# common.net
KiCad netlist of a schematic drawn in EAGLE
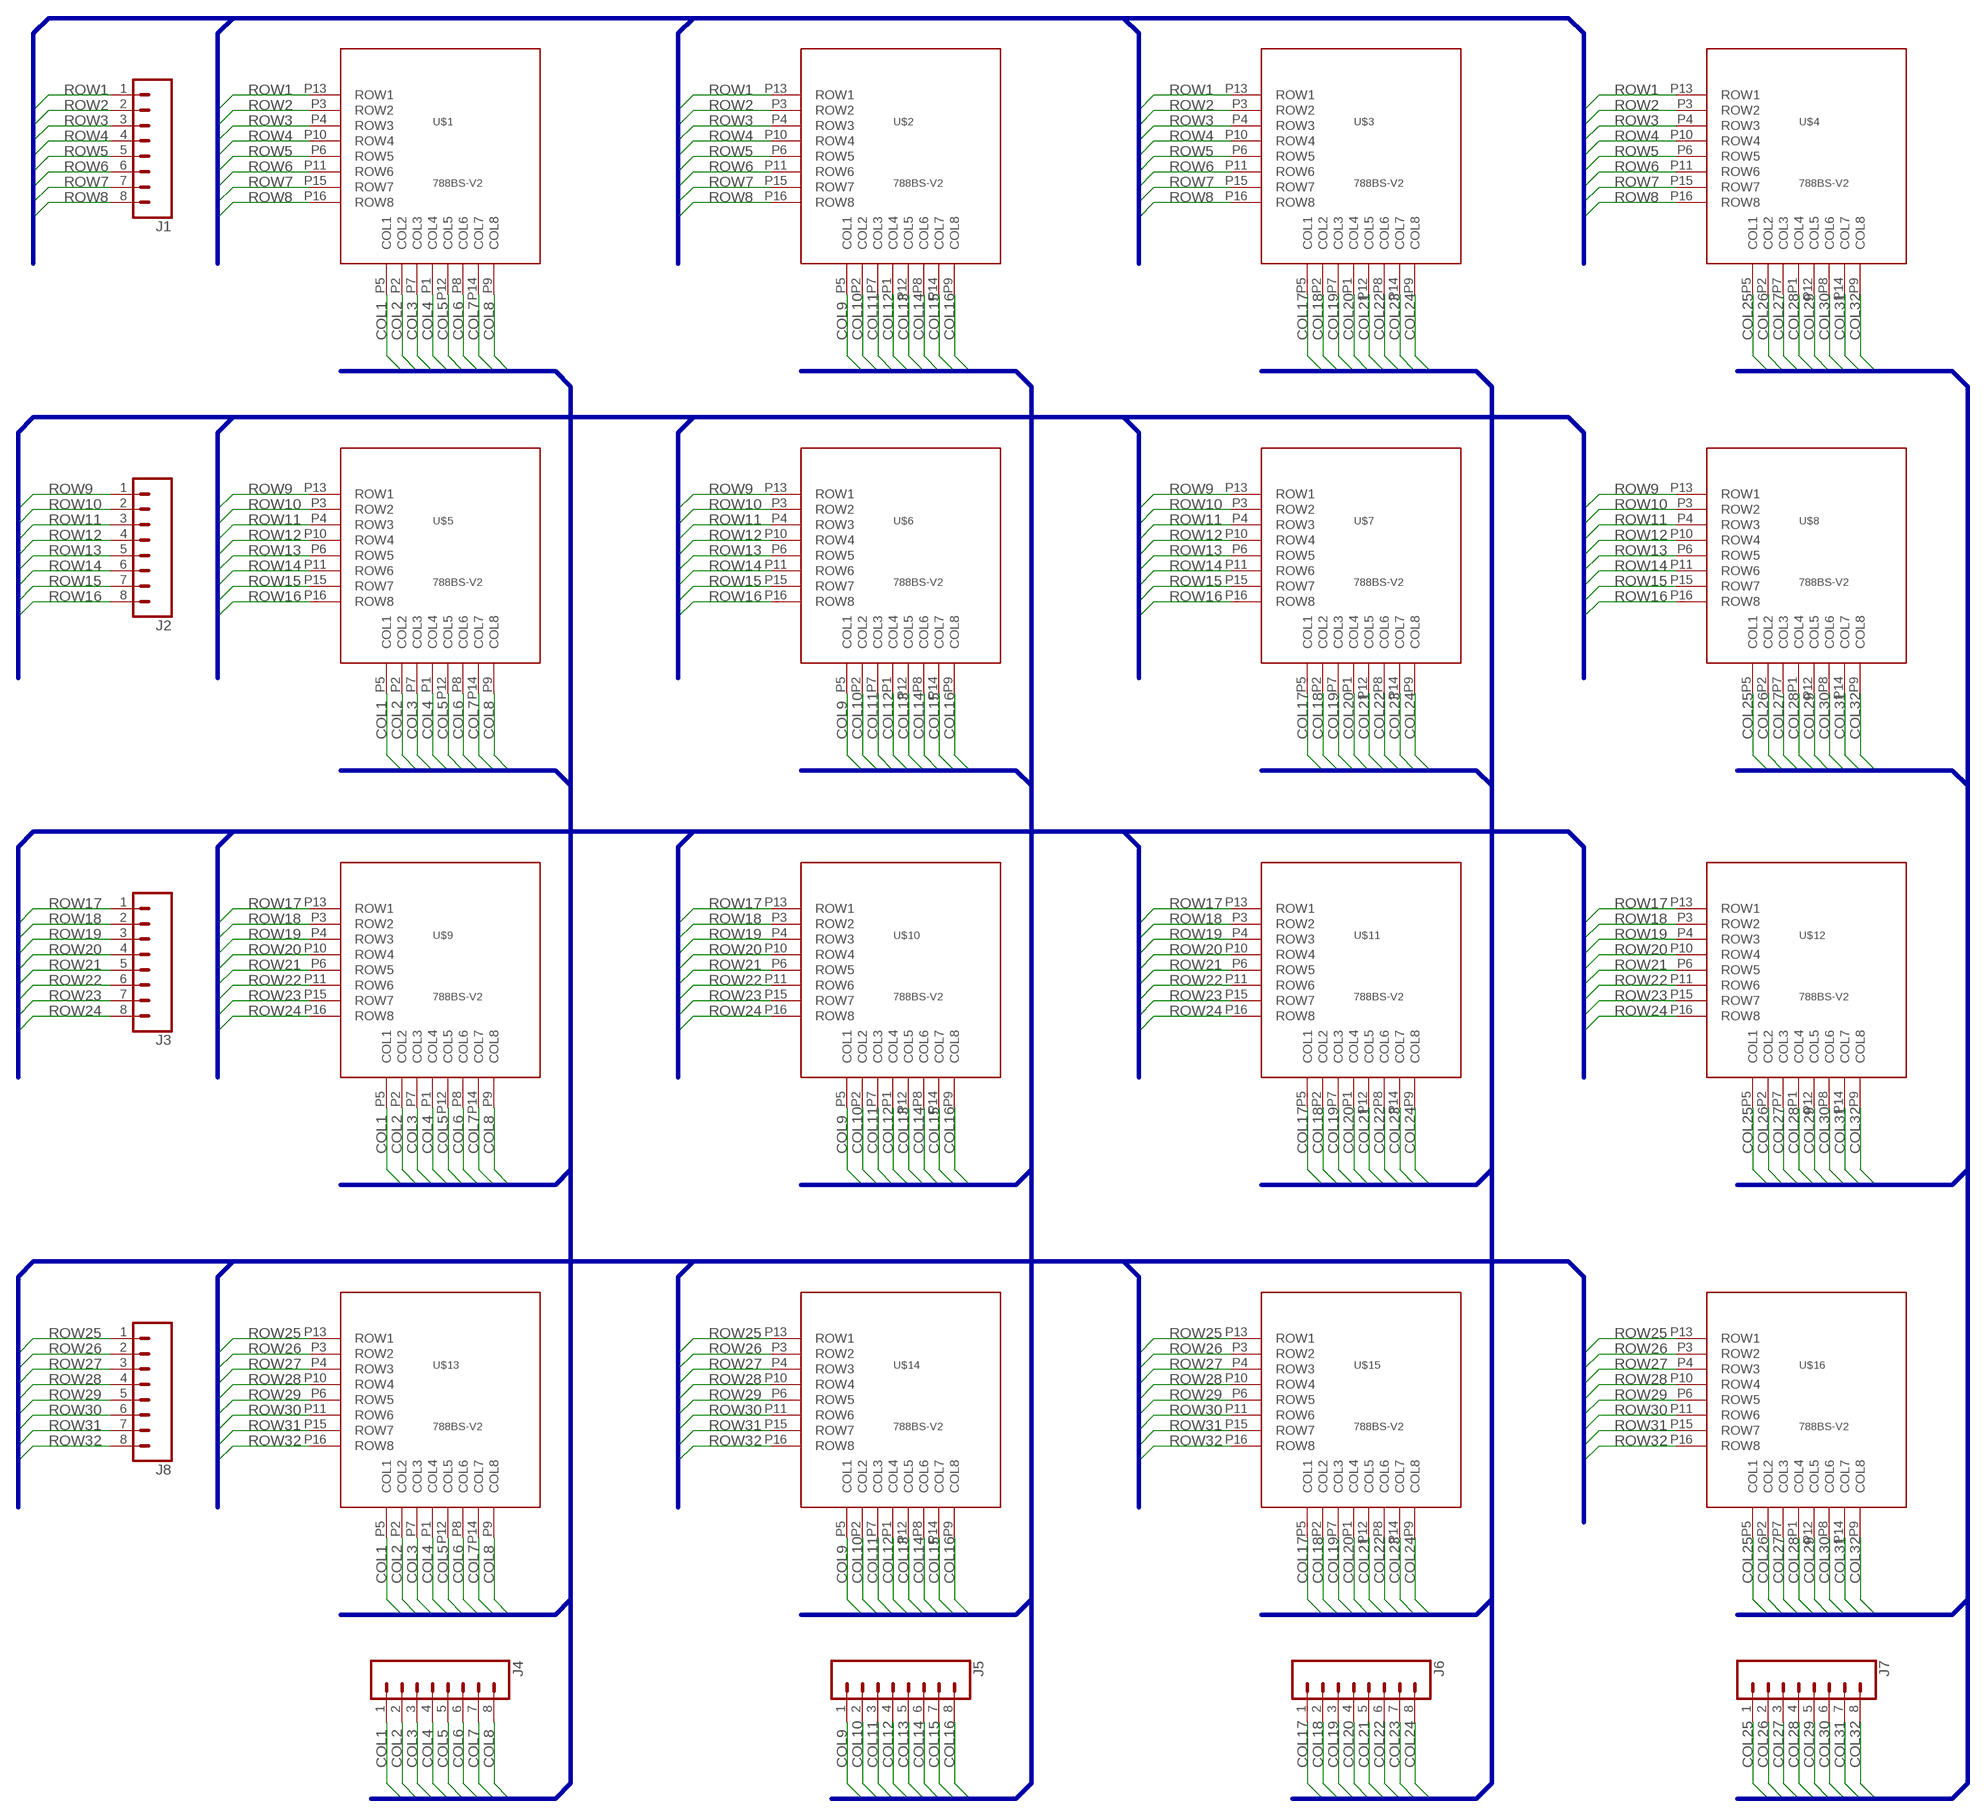
[diagram p0: schematic, sheet 1]

(export (version "E")
  (design (tool "Eeschema 10.0.6"))
  (components
    (comp (ref "J1")
      (value "CONN_08\"")
      (footprint "eagle-import:1X08")
      (libsource (lib "eagle-import") (part "CONN_08{dblquote}"))
    )
    (comp (ref "J2")
      (value "CONN_08\"")
      (footprint "eagle-import:1X08")
      (libsource (lib "eagle-import") (part "CONN_08{dblquote}"))
    )
    (comp (ref "J3")
      (value "CONN_08\"")
      (footprint "eagle-import:1X08")
      (libsource (lib "eagle-import") (part "CONN_08{dblquote}"))
    )
    (comp (ref "J4")
      (value "CONN_08\"")
      (footprint "eagle-import:1X08")
      (libsource (lib "eagle-import") (part "CONN_08{dblquote}"))
    )
    (comp (ref "J5")
      (value "CONN_08\"")
      (footprint "eagle-import:1X08")
      (libsource (lib "eagle-import") (part "CONN_08{dblquote}"))
    )
    (comp (ref "J6")
      (value "CONN_08\"")
      (footprint "eagle-import:1X08")
      (libsource (lib "eagle-import") (part "CONN_08{dblquote}"))
    )
    (comp (ref "J7")
      (value "CONN_08\"")
      (footprint "eagle-import:1X08")
      (libsource (lib "eagle-import") (part "CONN_08{dblquote}"))
    )
    (comp (ref "J8")
      (value "CONN_08\"")
      (footprint "eagle-import:1X08")
      (libsource (lib "eagle-import") (part "CONN_08{dblquote}"))
    )
    (comp (ref "U$1")
      (value "788BS-V2")
      (footprint "eagle-import:788BS8X81.9MM-V2")
      (libsource (lib "eagle-import") (part "788BS-V2"))
    )
    (comp (ref "U$2")
      (value "788BS-V2")
      (footprint "eagle-import:788BS8X81.9MM-V2")
      (libsource (lib "eagle-import") (part "788BS-V2"))
    )
    (comp (ref "U$3")
      (value "788BS-V2")
      (footprint "eagle-import:788BS8X81.9MM-V2")
      (libsource (lib "eagle-import") (part "788BS-V2"))
    )
    (comp (ref "U$4")
      (value "788BS-V2")
      (footprint "eagle-import:788BS8X81.9MM-V2")
      (libsource (lib "eagle-import") (part "788BS-V2"))
    )
    (comp (ref "U$5")
      (value "788BS-V2")
      (footprint "eagle-import:788BS8X81.9MM-V2")
      (libsource (lib "eagle-import") (part "788BS-V2"))
    )
    (comp (ref "U$6")
      (value "788BS-V2")
      (footprint "eagle-import:788BS8X81.9MM-V2")
      (libsource (lib "eagle-import") (part "788BS-V2"))
    )
    (comp (ref "U$7")
      (value "788BS-V2")
      (footprint "eagle-import:788BS8X81.9MM-V2")
      (libsource (lib "eagle-import") (part "788BS-V2"))
    )
    (comp (ref "U$8")
      (value "788BS-V2")
      (footprint "eagle-import:788BS8X81.9MM-V2")
      (libsource (lib "eagle-import") (part "788BS-V2"))
    )
    (comp (ref "U$9")
      (value "788BS-V2")
      (footprint "eagle-import:788BS8X81.9MM-V2")
      (libsource (lib "eagle-import") (part "788BS-V2"))
    )
    (comp (ref "U$10")
      (value "788BS-V2")
      (footprint "eagle-import:788BS8X81.9MM-V2")
      (libsource (lib "eagle-import") (part "788BS-V2"))
    )
    (comp (ref "U$11")
      (value "788BS-V2")
      (footprint "eagle-import:788BS8X81.9MM-V2")
      (libsource (lib "eagle-import") (part "788BS-V2"))
    )
    (comp (ref "U$12")
      (value "788BS-V2")
      (footprint "eagle-import:788BS8X81.9MM-V2")
      (libsource (lib "eagle-import") (part "788BS-V2"))
    )
    (comp (ref "U$13")
      (value "788BS-V2")
      (footprint "eagle-import:788BS8X81.9MM-V2")
      (libsource (lib "eagle-import") (part "788BS-V2"))
    )
    (comp (ref "U$14")
      (value "788BS-V2")
      (footprint "eagle-import:788BS8X81.9MM-V2")
      (libsource (lib "eagle-import") (part "788BS-V2"))
    )
    (comp (ref "U$15")
      (value "788BS-V2")
      (footprint "eagle-import:788BS8X81.9MM-V2")
      (libsource (lib "eagle-import") (part "788BS-V2"))
    )
    (comp (ref "U$16")
      (value "788BS-V2")
      (footprint "eagle-import:788BS8X81.9MM-V2")
      (libsource (lib "eagle-import") (part "788BS-V2"))
    )
  )
  (nets
    (net (code "57") (name "/COL1") (class "Default")
      (node (ref "J4") (pin "1") (pinfunction "1_1") (pintype "passive"))
      (node (ref "U$1") (pin "P5") (pinfunction "COL1_P5") (pintype "bidirectional"))
      (node (ref "U$13") (pin "P5") (pinfunction "COL1_P5") (pintype "bidirectional"))
      (node (ref "U$5") (pin "P5") (pinfunction "COL1_P5") (pintype "bidirectional"))
      (node (ref "U$9") (pin "P5") (pinfunction "COL1_P5") (pintype "bidirectional"))
    )
    (net (code "58") (name "/COL2") (class "Default")
      (node (ref "J4") (pin "2") (pinfunction "2_2") (pintype "passive"))
      (node (ref "U$1") (pin "P2") (pinfunction "COL2_P2") (pintype "bidirectional"))
      (node (ref "U$13") (pin "P2") (pinfunction "COL2_P2") (pintype "bidirectional"))
      (node (ref "U$5") (pin "P2") (pinfunction "COL2_P2") (pintype "bidirectional"))
      (node (ref "U$9") (pin "P2") (pinfunction "COL2_P2") (pintype "bidirectional"))
    )
    (net (code "59") (name "/COL3") (class "Default")
      (node (ref "J4") (pin "3") (pinfunction "3_3") (pintype "passive"))
      (node (ref "U$1") (pin "P7") (pinfunction "COL3_P7") (pintype "bidirectional"))
      (node (ref "U$13") (pin "P7") (pinfunction "COL3_P7") (pintype "bidirectional"))
      (node (ref "U$5") (pin "P7") (pinfunction "COL3_P7") (pintype "bidirectional"))
      (node (ref "U$9") (pin "P7") (pinfunction "COL3_P7") (pintype "bidirectional"))
    )
    (net (code "60") (name "/COL4") (class "Default")
      (node (ref "J4") (pin "4") (pinfunction "4_4") (pintype "passive"))
      (node (ref "U$1") (pin "P1") (pinfunction "COL4_P1") (pintype "bidirectional"))
      (node (ref "U$13") (pin "P1") (pinfunction "COL4_P1") (pintype "bidirectional"))
      (node (ref "U$5") (pin "P1") (pinfunction "COL4_P1") (pintype "bidirectional"))
      (node (ref "U$9") (pin "P1") (pinfunction "COL4_P1") (pintype "bidirectional"))
    )
    (net (code "61") (name "/COL5") (class "Default")
      (node (ref "J4") (pin "5") (pinfunction "5_5") (pintype "passive"))
      (node (ref "U$1") (pin "P12") (pinfunction "COL5_P12") (pintype "bidirectional"))
      (node (ref "U$13") (pin "P12") (pinfunction "COL5_P12") (pintype "bidirectional"))
      (node (ref "U$5") (pin "P12") (pinfunction "COL5_P12") (pintype "bidirectional"))
      (node (ref "U$9") (pin "P12") (pinfunction "COL5_P12") (pintype "bidirectional"))
    )
    (net (code "62") (name "/COL6") (class "Default")
      (node (ref "J4") (pin "6") (pinfunction "6_6") (pintype "passive"))
      (node (ref "U$1") (pin "P8") (pinfunction "COL6_P8") (pintype "bidirectional"))
      (node (ref "U$13") (pin "P8") (pinfunction "COL6_P8") (pintype "bidirectional"))
      (node (ref "U$5") (pin "P8") (pinfunction "COL6_P8") (pintype "bidirectional"))
      (node (ref "U$9") (pin "P8") (pinfunction "COL6_P8") (pintype "bidirectional"))
    )
    (net (code "63") (name "/COL7") (class "Default")
      (node (ref "J4") (pin "7") (pinfunction "7_7") (pintype "passive"))
      (node (ref "U$1") (pin "P14") (pinfunction "COL7_P14") (pintype "bidirectional"))
      (node (ref "U$13") (pin "P14") (pinfunction "COL7_P14") (pintype "bidirectional"))
      (node (ref "U$5") (pin "P14") (pinfunction "COL7_P14") (pintype "bidirectional"))
      (node (ref "U$9") (pin "P14") (pinfunction "COL7_P14") (pintype "bidirectional"))
    )
    (net (code "64") (name "/COL8") (class "Default")
      (node (ref "J4") (pin "8") (pinfunction "8_8") (pintype "passive"))
      (node (ref "U$1") (pin "P9") (pinfunction "COL8_P9") (pintype "bidirectional"))
      (node (ref "U$13") (pin "P9") (pinfunction "COL8_P9") (pintype "bidirectional"))
      (node (ref "U$5") (pin "P9") (pinfunction "COL8_P9") (pintype "bidirectional"))
      (node (ref "U$9") (pin "P9") (pinfunction "COL8_P9") (pintype "bidirectional"))
    )
    (net (code "65") (name "/COL9") (class "Default")
      (node (ref "J5") (pin "1") (pinfunction "1_1") (pintype "passive"))
      (node (ref "U$10") (pin "P5") (pinfunction "COL1_P5") (pintype "bidirectional"))
      (node (ref "U$14") (pin "P5") (pinfunction "COL1_P5") (pintype "bidirectional"))
      (node (ref "U$2") (pin "P5") (pinfunction "COL1_P5") (pintype "bidirectional"))
      (node (ref "U$6") (pin "P5") (pinfunction "COL1_P5") (pintype "bidirectional"))
    )
    (net (code "66") (name "/COL10") (class "Default")
      (node (ref "J5") (pin "2") (pinfunction "2_2") (pintype "passive"))
      (node (ref "U$10") (pin "P2") (pinfunction "COL2_P2") (pintype "bidirectional"))
      (node (ref "U$14") (pin "P2") (pinfunction "COL2_P2") (pintype "bidirectional"))
      (node (ref "U$2") (pin "P2") (pinfunction "COL2_P2") (pintype "bidirectional"))
      (node (ref "U$6") (pin "P2") (pinfunction "COL2_P2") (pintype "bidirectional"))
    )
    (net (code "67") (name "/COL11") (class "Default")
      (node (ref "J5") (pin "3") (pinfunction "3_3") (pintype "passive"))
      (node (ref "U$10") (pin "P7") (pinfunction "COL3_P7") (pintype "bidirectional"))
      (node (ref "U$14") (pin "P7") (pinfunction "COL3_P7") (pintype "bidirectional"))
      (node (ref "U$2") (pin "P7") (pinfunction "COL3_P7") (pintype "bidirectional"))
      (node (ref "U$6") (pin "P7") (pinfunction "COL3_P7") (pintype "bidirectional"))
    )
    (net (code "68") (name "/COL12") (class "Default")
      (node (ref "J5") (pin "4") (pinfunction "4_4") (pintype "passive"))
      (node (ref "U$10") (pin "P1") (pinfunction "COL4_P1") (pintype "bidirectional"))
      (node (ref "U$14") (pin "P1") (pinfunction "COL4_P1") (pintype "bidirectional"))
      (node (ref "U$2") (pin "P1") (pinfunction "COL4_P1") (pintype "bidirectional"))
      (node (ref "U$6") (pin "P1") (pinfunction "COL4_P1") (pintype "bidirectional"))
    )
    (net (code "69") (name "/COL13") (class "Default")
      (node (ref "J5") (pin "5") (pinfunction "5_5") (pintype "passive"))
      (node (ref "U$10") (pin "P12") (pinfunction "COL5_P12") (pintype "bidirectional"))
      (node (ref "U$14") (pin "P12") (pinfunction "COL5_P12") (pintype "bidirectional"))
      (node (ref "U$2") (pin "P12") (pinfunction "COL5_P12") (pintype "bidirectional"))
      (node (ref "U$6") (pin "P12") (pinfunction "COL5_P12") (pintype "bidirectional"))
    )
    (net (code "70") (name "/COL14") (class "Default")
      (node (ref "J5") (pin "6") (pinfunction "6_6") (pintype "passive"))
      (node (ref "U$10") (pin "P8") (pinfunction "COL6_P8") (pintype "bidirectional"))
      (node (ref "U$14") (pin "P8") (pinfunction "COL6_P8") (pintype "bidirectional"))
      (node (ref "U$2") (pin "P8") (pinfunction "COL6_P8") (pintype "bidirectional"))
      (node (ref "U$6") (pin "P8") (pinfunction "COL6_P8") (pintype "bidirectional"))
    )
    (net (code "71") (name "/COL15") (class "Default")
      (node (ref "J5") (pin "7") (pinfunction "7_7") (pintype "passive"))
      (node (ref "U$10") (pin "P14") (pinfunction "COL7_P14") (pintype "bidirectional"))
      (node (ref "U$14") (pin "P14") (pinfunction "COL7_P14") (pintype "bidirectional"))
      (node (ref "U$2") (pin "P14") (pinfunction "COL7_P14") (pintype "bidirectional"))
      (node (ref "U$6") (pin "P14") (pinfunction "COL7_P14") (pintype "bidirectional"))
    )
    (net (code "72") (name "/COL16") (class "Default")
      (node (ref "J5") (pin "8") (pinfunction "8_8") (pintype "passive"))
      (node (ref "U$10") (pin "P9") (pinfunction "COL8_P9") (pintype "bidirectional"))
      (node (ref "U$14") (pin "P9") (pinfunction "COL8_P9") (pintype "bidirectional"))
      (node (ref "U$2") (pin "P9") (pinfunction "COL8_P9") (pintype "bidirectional"))
      (node (ref "U$6") (pin "P9") (pinfunction "COL8_P9") (pintype "bidirectional"))
    )
    (net (code "73") (name "/COL17") (class "Default")
      (node (ref "J6") (pin "1") (pinfunction "1_1") (pintype "passive"))
      (node (ref "U$11") (pin "P5") (pinfunction "COL1_P5") (pintype "bidirectional"))
      (node (ref "U$15") (pin "P5") (pinfunction "COL1_P5") (pintype "bidirectional"))
      (node (ref "U$3") (pin "P5") (pinfunction "COL1_P5") (pintype "bidirectional"))
      (node (ref "U$7") (pin "P5") (pinfunction "COL1_P5") (pintype "bidirectional"))
    )
    (net (code "74") (name "/COL18") (class "Default")
      (node (ref "J6") (pin "2") (pinfunction "2_2") (pintype "passive"))
      (node (ref "U$11") (pin "P2") (pinfunction "COL2_P2") (pintype "bidirectional"))
      (node (ref "U$15") (pin "P2") (pinfunction "COL2_P2") (pintype "bidirectional"))
      (node (ref "U$3") (pin "P2") (pinfunction "COL2_P2") (pintype "bidirectional"))
      (node (ref "U$7") (pin "P2") (pinfunction "COL2_P2") (pintype "bidirectional"))
    )
    (net (code "75") (name "/COL19") (class "Default")
      (node (ref "J6") (pin "3") (pinfunction "3_3") (pintype "passive"))
      (node (ref "U$11") (pin "P7") (pinfunction "COL3_P7") (pintype "bidirectional"))
      (node (ref "U$15") (pin "P7") (pinfunction "COL3_P7") (pintype "bidirectional"))
      (node (ref "U$3") (pin "P7") (pinfunction "COL3_P7") (pintype "bidirectional"))
      (node (ref "U$7") (pin "P7") (pinfunction "COL3_P7") (pintype "bidirectional"))
    )
    (net (code "76") (name "/COL20") (class "Default")
      (node (ref "J6") (pin "4") (pinfunction "4_4") (pintype "passive"))
      (node (ref "U$11") (pin "P1") (pinfunction "COL4_P1") (pintype "bidirectional"))
      (node (ref "U$15") (pin "P1") (pinfunction "COL4_P1") (pintype "bidirectional"))
      (node (ref "U$3") (pin "P1") (pinfunction "COL4_P1") (pintype "bidirectional"))
      (node (ref "U$7") (pin "P1") (pinfunction "COL4_P1") (pintype "bidirectional"))
    )
    (net (code "77") (name "/COL21") (class "Default")
      (node (ref "J6") (pin "5") (pinfunction "5_5") (pintype "passive"))
      (node (ref "U$11") (pin "P12") (pinfunction "COL5_P12") (pintype "bidirectional"))
      (node (ref "U$15") (pin "P12") (pinfunction "COL5_P12") (pintype "bidirectional"))
      (node (ref "U$3") (pin "P12") (pinfunction "COL5_P12") (pintype "bidirectional"))
      (node (ref "U$7") (pin "P12") (pinfunction "COL5_P12") (pintype "bidirectional"))
    )
    (net (code "78") (name "/COL22") (class "Default")
      (node (ref "J6") (pin "6") (pinfunction "6_6") (pintype "passive"))
      (node (ref "U$11") (pin "P8") (pinfunction "COL6_P8") (pintype "bidirectional"))
      (node (ref "U$15") (pin "P8") (pinfunction "COL6_P8") (pintype "bidirectional"))
      (node (ref "U$3") (pin "P8") (pinfunction "COL6_P8") (pintype "bidirectional"))
      (node (ref "U$7") (pin "P8") (pinfunction "COL6_P8") (pintype "bidirectional"))
    )
    (net (code "79") (name "/COL23") (class "Default")
      (node (ref "J6") (pin "7") (pinfunction "7_7") (pintype "passive"))
      (node (ref "U$11") (pin "P14") (pinfunction "COL7_P14") (pintype "bidirectional"))
      (node (ref "U$15") (pin "P14") (pinfunction "COL7_P14") (pintype "bidirectional"))
      (node (ref "U$3") (pin "P14") (pinfunction "COL7_P14") (pintype "bidirectional"))
      (node (ref "U$7") (pin "P14") (pinfunction "COL7_P14") (pintype "bidirectional"))
    )
    (net (code "80") (name "/COL24") (class "Default")
      (node (ref "J6") (pin "8") (pinfunction "8_8") (pintype "passive"))
      (node (ref "U$11") (pin "P9") (pinfunction "COL8_P9") (pintype "bidirectional"))
      (node (ref "U$15") (pin "P9") (pinfunction "COL8_P9") (pintype "bidirectional"))
      (node (ref "U$3") (pin "P9") (pinfunction "COL8_P9") (pintype "bidirectional"))
      (node (ref "U$7") (pin "P9") (pinfunction "COL8_P9") (pintype "bidirectional"))
    )
    (net (code "81") (name "/COL25") (class "Default")
      (node (ref "J7") (pin "1") (pinfunction "1_1") (pintype "passive"))
      (node (ref "U$12") (pin "P5") (pinfunction "COL1_P5") (pintype "bidirectional"))
      (node (ref "U$16") (pin "P5") (pinfunction "COL1_P5") (pintype "bidirectional"))
      (node (ref "U$4") (pin "P5") (pinfunction "COL1_P5") (pintype "bidirectional"))
      (node (ref "U$8") (pin "P5") (pinfunction "COL1_P5") (pintype "bidirectional"))
    )
    (net (code "82") (name "/COL26") (class "Default")
      (node (ref "J7") (pin "2") (pinfunction "2_2") (pintype "passive"))
      (node (ref "U$12") (pin "P2") (pinfunction "COL2_P2") (pintype "bidirectional"))
      (node (ref "U$16") (pin "P2") (pinfunction "COL2_P2") (pintype "bidirectional"))
      (node (ref "U$4") (pin "P2") (pinfunction "COL2_P2") (pintype "bidirectional"))
      (node (ref "U$8") (pin "P2") (pinfunction "COL2_P2") (pintype "bidirectional"))
    )
    (net (code "83") (name "/COL27") (class "Default")
      (node (ref "J7") (pin "3") (pinfunction "3_3") (pintype "passive"))
      (node (ref "U$12") (pin "P7") (pinfunction "COL3_P7") (pintype "bidirectional"))
      (node (ref "U$16") (pin "P7") (pinfunction "COL3_P7") (pintype "bidirectional"))
      (node (ref "U$4") (pin "P7") (pinfunction "COL3_P7") (pintype "bidirectional"))
      (node (ref "U$8") (pin "P7") (pinfunction "COL3_P7") (pintype "bidirectional"))
    )
    (net (code "84") (name "/COL28") (class "Default")
      (node (ref "J7") (pin "4") (pinfunction "4_4") (pintype "passive"))
      (node (ref "U$12") (pin "P1") (pinfunction "COL4_P1") (pintype "bidirectional"))
      (node (ref "U$16") (pin "P1") (pinfunction "COL4_P1") (pintype "bidirectional"))
      (node (ref "U$4") (pin "P1") (pinfunction "COL4_P1") (pintype "bidirectional"))
      (node (ref "U$8") (pin "P1") (pinfunction "COL4_P1") (pintype "bidirectional"))
    )
    (net (code "85") (name "/COL29") (class "Default")
      (node (ref "J7") (pin "5") (pinfunction "5_5") (pintype "passive"))
      (node (ref "U$12") (pin "P12") (pinfunction "COL5_P12") (pintype "bidirectional"))
      (node (ref "U$16") (pin "P12") (pinfunction "COL5_P12") (pintype "bidirectional"))
      (node (ref "U$4") (pin "P12") (pinfunction "COL5_P12") (pintype "bidirectional"))
      (node (ref "U$8") (pin "P12") (pinfunction "COL5_P12") (pintype "bidirectional"))
    )
    (net (code "86") (name "/COL30") (class "Default")
      (node (ref "J7") (pin "6") (pinfunction "6_6") (pintype "passive"))
      (node (ref "U$12") (pin "P8") (pinfunction "COL6_P8") (pintype "bidirectional"))
      (node (ref "U$16") (pin "P8") (pinfunction "COL6_P8") (pintype "bidirectional"))
      (node (ref "U$4") (pin "P8") (pinfunction "COL6_P8") (pintype "bidirectional"))
      (node (ref "U$8") (pin "P8") (pinfunction "COL6_P8") (pintype "bidirectional"))
    )
    (net (code "87") (name "/COL31") (class "Default")
      (node (ref "J7") (pin "7") (pinfunction "7_7") (pintype "passive"))
      (node (ref "U$12") (pin "P14") (pinfunction "COL7_P14") (pintype "bidirectional"))
      (node (ref "U$16") (pin "P14") (pinfunction "COL7_P14") (pintype "bidirectional"))
      (node (ref "U$4") (pin "P14") (pinfunction "COL7_P14") (pintype "bidirectional"))
      (node (ref "U$8") (pin "P14") (pinfunction "COL7_P14") (pintype "bidirectional"))
    )
    (net (code "88") (name "/COL32") (class "Default")
      (node (ref "J7") (pin "8") (pinfunction "8_8") (pintype "passive"))
      (node (ref "U$12") (pin "P9") (pinfunction "COL8_P9") (pintype "bidirectional"))
      (node (ref "U$16") (pin "P9") (pinfunction "COL8_P9") (pintype "bidirectional"))
      (node (ref "U$4") (pin "P9") (pinfunction "COL8_P9") (pintype "bidirectional"))
      (node (ref "U$8") (pin "P9") (pinfunction "COL8_P9") (pintype "bidirectional"))
    )
    (net (code "89") (name "/ROW1") (class "Default")
      (node (ref "J1") (pin "1") (pinfunction "1_1") (pintype "passive"))
      (node (ref "U$1") (pin "P13") (pinfunction "ROW1_P13") (pintype "bidirectional"))
      (node (ref "U$2") (pin "P13") (pinfunction "ROW1_P13") (pintype "bidirectional"))
      (node (ref "U$3") (pin "P13") (pinfunction "ROW1_P13") (pintype "bidirectional"))
      (node (ref "U$4") (pin "P13") (pinfunction "ROW1_P13") (pintype "bidirectional"))
    )
    (net (code "90") (name "/ROW2") (class "Default")
      (node (ref "J1") (pin "2") (pinfunction "2_2") (pintype "passive"))
      (node (ref "U$1") (pin "P3") (pinfunction "ROW2_P3") (pintype "bidirectional"))
      (node (ref "U$2") (pin "P3") (pinfunction "ROW2_P3") (pintype "bidirectional"))
      (node (ref "U$3") (pin "P3") (pinfunction "ROW2_P3") (pintype "bidirectional"))
      (node (ref "U$4") (pin "P3") (pinfunction "ROW2_P3") (pintype "bidirectional"))
    )
    (net (code "91") (name "/ROW3") (class "Default")
      (node (ref "J1") (pin "3") (pinfunction "3_3") (pintype "passive"))
      (node (ref "U$1") (pin "P4") (pinfunction "ROW3_P4") (pintype "bidirectional"))
      (node (ref "U$2") (pin "P4") (pinfunction "ROW3_P4") (pintype "bidirectional"))
      (node (ref "U$3") (pin "P4") (pinfunction "ROW3_P4") (pintype "bidirectional"))
      (node (ref "U$4") (pin "P4") (pinfunction "ROW3_P4") (pintype "bidirectional"))
    )
    (net (code "92") (name "/ROW4") (class "Default")
      (node (ref "J1") (pin "4") (pinfunction "4_4") (pintype "passive"))
      (node (ref "U$1") (pin "P10") (pinfunction "ROW4_P10") (pintype "bidirectional"))
      (node (ref "U$2") (pin "P10") (pinfunction "ROW4_P10") (pintype "bidirectional"))
      (node (ref "U$3") (pin "P10") (pinfunction "ROW4_P10") (pintype "bidirectional"))
      (node (ref "U$4") (pin "P10") (pinfunction "ROW4_P10") (pintype "bidirectional"))
    )
    (net (code "93") (name "/ROW5") (class "Default")
      (node (ref "J1") (pin "5") (pinfunction "5_5") (pintype "passive"))
      (node (ref "U$1") (pin "P6") (pinfunction "ROW5_P6") (pintype "bidirectional"))
      (node (ref "U$2") (pin "P6") (pinfunction "ROW5_P6") (pintype "bidirectional"))
      (node (ref "U$3") (pin "P6") (pinfunction "ROW5_P6") (pintype "bidirectional"))
      (node (ref "U$4") (pin "P6") (pinfunction "ROW5_P6") (pintype "bidirectional"))
    )
    (net (code "94") (name "/ROW6") (class "Default")
      (node (ref "J1") (pin "6") (pinfunction "6_6") (pintype "passive"))
      (node (ref "U$1") (pin "P11") (pinfunction "ROW6_P11") (pintype "bidirectional"))
      (node (ref "U$2") (pin "P11") (pinfunction "ROW6_P11") (pintype "bidirectional"))
      (node (ref "U$3") (pin "P11") (pinfunction "ROW6_P11") (pintype "bidirectional"))
      (node (ref "U$4") (pin "P11") (pinfunction "ROW6_P11") (pintype "bidirectional"))
    )
    (net (code "95") (name "/ROW7") (class "Default")
      (node (ref "J1") (pin "7") (pinfunction "7_7") (pintype "passive"))
      (node (ref "U$1") (pin "P15") (pinfunction "ROW7_P15") (pintype "bidirectional"))
      (node (ref "U$2") (pin "P15") (pinfunction "ROW7_P15") (pintype "bidirectional"))
      (node (ref "U$3") (pin "P15") (pinfunction "ROW7_P15") (pintype "bidirectional"))
      (node (ref "U$4") (pin "P15") (pinfunction "ROW7_P15") (pintype "bidirectional"))
    )
    (net (code "96") (name "/ROW8") (class "Default")
      (node (ref "J1") (pin "8") (pinfunction "8_8") (pintype "passive"))
      (node (ref "U$1") (pin "P16") (pinfunction "ROW8_P16") (pintype "bidirectional"))
      (node (ref "U$2") (pin "P16") (pinfunction "ROW8_P16") (pintype "bidirectional"))
      (node (ref "U$3") (pin "P16") (pinfunction "ROW8_P16") (pintype "bidirectional"))
      (node (ref "U$4") (pin "P16") (pinfunction "ROW8_P16") (pintype "bidirectional"))
    )
    (net (code "97") (name "/ROW9") (class "Default")
      (node (ref "J2") (pin "1") (pinfunction "1_1") (pintype "passive"))
      (node (ref "U$5") (pin "P13") (pinfunction "ROW1_P13") (pintype "bidirectional"))
      (node (ref "U$6") (pin "P13") (pinfunction "ROW1_P13") (pintype "bidirectional"))
      (node (ref "U$7") (pin "P13") (pinfunction "ROW1_P13") (pintype "bidirectional"))
      (node (ref "U$8") (pin "P13") (pinfunction "ROW1_P13") (pintype "bidirectional"))
    )
    (net (code "98") (name "/ROW10") (class "Default")
      (node (ref "J2") (pin "2") (pinfunction "2_2") (pintype "passive"))
      (node (ref "U$5") (pin "P3") (pinfunction "ROW2_P3") (pintype "bidirectional"))
      (node (ref "U$6") (pin "P3") (pinfunction "ROW2_P3") (pintype "bidirectional"))
      (node (ref "U$7") (pin "P3") (pinfunction "ROW2_P3") (pintype "bidirectional"))
      (node (ref "U$8") (pin "P3") (pinfunction "ROW2_P3") (pintype "bidirectional"))
    )
    (net (code "99") (name "/ROW11") (class "Default")
      (node (ref "J2") (pin "3") (pinfunction "3_3") (pintype "passive"))
      (node (ref "U$5") (pin "P4") (pinfunction "ROW3_P4") (pintype "bidirectional"))
      (node (ref "U$6") (pin "P4") (pinfunction "ROW3_P4") (pintype "bidirectional"))
      (node (ref "U$7") (pin "P4") (pinfunction "ROW3_P4") (pintype "bidirectional"))
      (node (ref "U$8") (pin "P4") (pinfunction "ROW3_P4") (pintype "bidirectional"))
    )
    (net (code "100") (name "/ROW12") (class "Default")
      (node (ref "J2") (pin "4") (pinfunction "4_4") (pintype "passive"))
      (node (ref "U$5") (pin "P10") (pinfunction "ROW4_P10") (pintype "bidirectional"))
      (node (ref "U$6") (pin "P10") (pinfunction "ROW4_P10") (pintype "bidirectional"))
      (node (ref "U$7") (pin "P10") (pinfunction "ROW4_P10") (pintype "bidirectional"))
      (node (ref "U$8") (pin "P10") (pinfunction "ROW4_P10") (pintype "bidirectional"))
    )
    (net (code "101") (name "/ROW13") (class "Default")
      (node (ref "J2") (pin "5") (pinfunction "5_5") (pintype "passive"))
      (node (ref "U$5") (pin "P6") (pinfunction "ROW5_P6") (pintype "bidirectional"))
      (node (ref "U$6") (pin "P6") (pinfunction "ROW5_P6") (pintype "bidirectional"))
      (node (ref "U$7") (pin "P6") (pinfunction "ROW5_P6") (pintype "bidirectional"))
      (node (ref "U$8") (pin "P6") (pinfunction "ROW5_P6") (pintype "bidirectional"))
    )
    (net (code "102") (name "/ROW14") (class "Default")
      (node (ref "J2") (pin "6") (pinfunction "6_6") (pintype "passive"))
      (node (ref "U$5") (pin "P11") (pinfunction "ROW6_P11") (pintype "bidirectional"))
      (node (ref "U$6") (pin "P11") (pinfunction "ROW6_P11") (pintype "bidirectional"))
      (node (ref "U$7") (pin "P11") (pinfunction "ROW6_P11") (pintype "bidirectional"))
      (node (ref "U$8") (pin "P11") (pinfunction "ROW6_P11") (pintype "bidirectional"))
    )
    (net (code "103") (name "/ROW15") (class "Default")
      (node (ref "J2") (pin "7") (pinfunction "7_7") (pintype "passive"))
      (node (ref "U$5") (pin "P15") (pinfunction "ROW7_P15") (pintype "bidirectional"))
      (node (ref "U$6") (pin "P15") (pinfunction "ROW7_P15") (pintype "bidirectional"))
      (node (ref "U$7") (pin "P15") (pinfunction "ROW7_P15") (pintype "bidirectional"))
      (node (ref "U$8") (pin "P15") (pinfunction "ROW7_P15") (pintype "bidirectional"))
    )
    (net (code "104") (name "/ROW16") (class "Default")
      (node (ref "J2") (pin "8") (pinfunction "8_8") (pintype "passive"))
      (node (ref "U$5") (pin "P16") (pinfunction "ROW8_P16") (pintype "bidirectional"))
      (node (ref "U$6") (pin "P16") (pinfunction "ROW8_P16") (pintype "bidirectional"))
      (node (ref "U$7") (pin "P16") (pinfunction "ROW8_P16") (pintype "bidirectional"))
      (node (ref "U$8") (pin "P16") (pinfunction "ROW8_P16") (pintype "bidirectional"))
    )
    (net (code "105") (name "/ROW17") (class "Default")
      (node (ref "J3") (pin "1") (pinfunction "1_1") (pintype "passive"))
      (node (ref "U$10") (pin "P13") (pinfunction "ROW1_P13") (pintype "bidirectional"))
      (node (ref "U$11") (pin "P13") (pinfunction "ROW1_P13") (pintype "bidirectional"))
      (node (ref "U$12") (pin "P13") (pinfunction "ROW1_P13") (pintype "bidirectional"))
      (node (ref "U$9") (pin "P13") (pinfunction "ROW1_P13") (pintype "bidirectional"))
    )
    (net (code "106") (name "/ROW18") (class "Default")
      (node (ref "J3") (pin "2") (pinfunction "2_2") (pintype "passive"))
      (node (ref "U$10") (pin "P3") (pinfunction "ROW2_P3") (pintype "bidirectional"))
      (node (ref "U$11") (pin "P3") (pinfunction "ROW2_P3") (pintype "bidirectional"))
      (node (ref "U$12") (pin "P3") (pinfunction "ROW2_P3") (pintype "bidirectional"))
      (node (ref "U$9") (pin "P3") (pinfunction "ROW2_P3") (pintype "bidirectional"))
    )
    (net (code "107") (name "/ROW19") (class "Default")
      (node (ref "J3") (pin "3") (pinfunction "3_3") (pintype "passive"))
      (node (ref "U$10") (pin "P4") (pinfunction "ROW3_P4") (pintype "bidirectional"))
      (node (ref "U$11") (pin "P4") (pinfunction "ROW3_P4") (pintype "bidirectional"))
      (node (ref "U$12") (pin "P4") (pinfunction "ROW3_P4") (pintype "bidirectional"))
      (node (ref "U$9") (pin "P4") (pinfunction "ROW3_P4") (pintype "bidirectional"))
    )
    (net (code "108") (name "/ROW20") (class "Default")
      (node (ref "J3") (pin "4") (pinfunction "4_4") (pintype "passive"))
      (node (ref "U$10") (pin "P10") (pinfunction "ROW4_P10") (pintype "bidirectional"))
      (node (ref "U$11") (pin "P10") (pinfunction "ROW4_P10") (pintype "bidirectional"))
      (node (ref "U$12") (pin "P10") (pinfunction "ROW4_P10") (pintype "bidirectional"))
      (node (ref "U$9") (pin "P10") (pinfunction "ROW4_P10") (pintype "bidirectional"))
    )
    (net (code "109") (name "/ROW21") (class "Default")
      (node (ref "J3") (pin "5") (pinfunction "5_5") (pintype "passive"))
      (node (ref "U$10") (pin "P6") (pinfunction "ROW5_P6") (pintype "bidirectional"))
      (node (ref "U$11") (pin "P6") (pinfunction "ROW5_P6") (pintype "bidirectional"))
      (node (ref "U$12") (pin "P6") (pinfunction "ROW5_P6") (pintype "bidirectional"))
      (node (ref "U$9") (pin "P6") (pinfunction "ROW5_P6") (pintype "bidirectional"))
    )
    (net (code "110") (name "/ROW22") (class "Default")
      (node (ref "J3") (pin "6") (pinfunction "6_6") (pintype "passive"))
      (node (ref "U$10") (pin "P11") (pinfunction "ROW6_P11") (pintype "bidirectional"))
      (node (ref "U$11") (pin "P11") (pinfunction "ROW6_P11") (pintype "bidirectional"))
      (node (ref "U$12") (pin "P11") (pinfunction "ROW6_P11") (pintype "bidirectional"))
      (node (ref "U$9") (pin "P11") (pinfunction "ROW6_P11") (pintype "bidirectional"))
    )
    (net (code "111") (name "/ROW23") (class "Default")
      (node (ref "J3") (pin "7") (pinfunction "7_7") (pintype "passive"))
      (node (ref "U$10") (pin "P15") (pinfunction "ROW7_P15") (pintype "bidirectional"))
      (node (ref "U$11") (pin "P15") (pinfunction "ROW7_P15") (pintype "bidirectional"))
      (node (ref "U$12") (pin "P15") (pinfunction "ROW7_P15") (pintype "bidirectional"))
      (node (ref "U$9") (pin "P15") (pinfunction "ROW7_P15") (pintype "bidirectional"))
    )
    (net (code "112") (name "/ROW24") (class "Default")
      (node (ref "J3") (pin "8") (pinfunction "8_8") (pintype "passive"))
      (node (ref "U$10") (pin "P16") (pinfunction "ROW8_P16") (pintype "bidirectional"))
      (node (ref "U$11") (pin "P16") (pinfunction "ROW8_P16") (pintype "bidirectional"))
      (node (ref "U$12") (pin "P16") (pinfunction "ROW8_P16") (pintype "bidirectional"))
      (node (ref "U$9") (pin "P16") (pinfunction "ROW8_P16") (pintype "bidirectional"))
    )
    (net (code "113") (name "/ROW25") (class "Default")
      (node (ref "J8") (pin "1") (pinfunction "1_1") (pintype "passive"))
      (node (ref "U$13") (pin "P13") (pinfunction "ROW1_P13") (pintype "bidirectional"))
      (node (ref "U$14") (pin "P13") (pinfunction "ROW1_P13") (pintype "bidirectional"))
      (node (ref "U$15") (pin "P13") (pinfunction "ROW1_P13") (pintype "bidirectional"))
      (node (ref "U$16") (pin "P13") (pinfunction "ROW1_P13") (pintype "bidirectional"))
    )
    (net (code "114") (name "/ROW26") (class "Default")
      (node (ref "J8") (pin "2") (pinfunction "2_2") (pintype "passive"))
      (node (ref "U$13") (pin "P3") (pinfunction "ROW2_P3") (pintype "bidirectional"))
      (node (ref "U$14") (pin "P3") (pinfunction "ROW2_P3") (pintype "bidirectional"))
      (node (ref "U$15") (pin "P3") (pinfunction "ROW2_P3") (pintype "bidirectional"))
      (node (ref "U$16") (pin "P3") (pinfunction "ROW2_P3") (pintype "bidirectional"))
    )
    (net (code "115") (name "/ROW27") (class "Default")
      (node (ref "J8") (pin "3") (pinfunction "3_3") (pintype "passive"))
      (node (ref "U$13") (pin "P4") (pinfunction "ROW3_P4") (pintype "bidirectional"))
      (node (ref "U$14") (pin "P4") (pinfunction "ROW3_P4") (pintype "bidirectional"))
      (node (ref "U$15") (pin "P4") (pinfunction "ROW3_P4") (pintype "bidirectional"))
      (node (ref "U$16") (pin "P4") (pinfunction "ROW3_P4") (pintype "bidirectional"))
    )
    (net (code "116") (name "/ROW28") (class "Default")
      (node (ref "J8") (pin "4") (pinfunction "4_4") (pintype "passive"))
      (node (ref "U$13") (pin "P10") (pinfunction "ROW4_P10") (pintype "bidirectional"))
      (node (ref "U$14") (pin "P10") (pinfunction "ROW4_P10") (pintype "bidirectional"))
      (node (ref "U$15") (pin "P10") (pinfunction "ROW4_P10") (pintype "bidirectional"))
      (node (ref "U$16") (pin "P10") (pinfunction "ROW4_P10") (pintype "bidirectional"))
    )
    (net (code "117") (name "/ROW29") (class "Default")
      (node (ref "J8") (pin "5") (pinfunction "5_5") (pintype "passive"))
      (node (ref "U$13") (pin "P6") (pinfunction "ROW5_P6") (pintype "bidirectional"))
      (node (ref "U$14") (pin "P6") (pinfunction "ROW5_P6") (pintype "bidirectional"))
      (node (ref "U$15") (pin "P6") (pinfunction "ROW5_P6") (pintype "bidirectional"))
      (node (ref "U$16") (pin "P6") (pinfunction "ROW5_P6") (pintype "bidirectional"))
    )
    (net (code "118") (name "/ROW30") (class "Default")
      (node (ref "J8") (pin "6") (pinfunction "6_6") (pintype "passive"))
      (node (ref "U$13") (pin "P11") (pinfunction "ROW6_P11") (pintype "bidirectional"))
      (node (ref "U$14") (pin "P11") (pinfunction "ROW6_P11") (pintype "bidirectional"))
      (node (ref "U$15") (pin "P11") (pinfunction "ROW6_P11") (pintype "bidirectional"))
      (node (ref "U$16") (pin "P11") (pinfunction "ROW6_P11") (pintype "bidirectional"))
    )
    (net (code "119") (name "/ROW31") (class "Default")
      (node (ref "J8") (pin "7") (pinfunction "7_7") (pintype "passive"))
      (node (ref "U$13") (pin "P15") (pinfunction "ROW7_P15") (pintype "bidirectional"))
      (node (ref "U$14") (pin "P15") (pinfunction "ROW7_P15") (pintype "bidirectional"))
      (node (ref "U$15") (pin "P15") (pinfunction "ROW7_P15") (pintype "bidirectional"))
      (node (ref "U$16") (pin "P15") (pinfunction "ROW7_P15") (pintype "bidirectional"))
    )
    (net (code "120") (name "/ROW32") (class "Default")
      (node (ref "J8") (pin "8") (pinfunction "8_8") (pintype "passive"))
      (node (ref "U$13") (pin "P16") (pinfunction "ROW8_P16") (pintype "bidirectional"))
      (node (ref "U$14") (pin "P16") (pinfunction "ROW8_P16") (pintype "bidirectional"))
      (node (ref "U$15") (pin "P16") (pinfunction "ROW8_P16") (pintype "bidirectional"))
      (node (ref "U$16") (pin "P16") (pinfunction "ROW8_P16") (pintype "bidirectional"))
    )
  )
)
